# HMI_SENSOR.net
KiCad netlist of a schematic drawn in Altium Designer
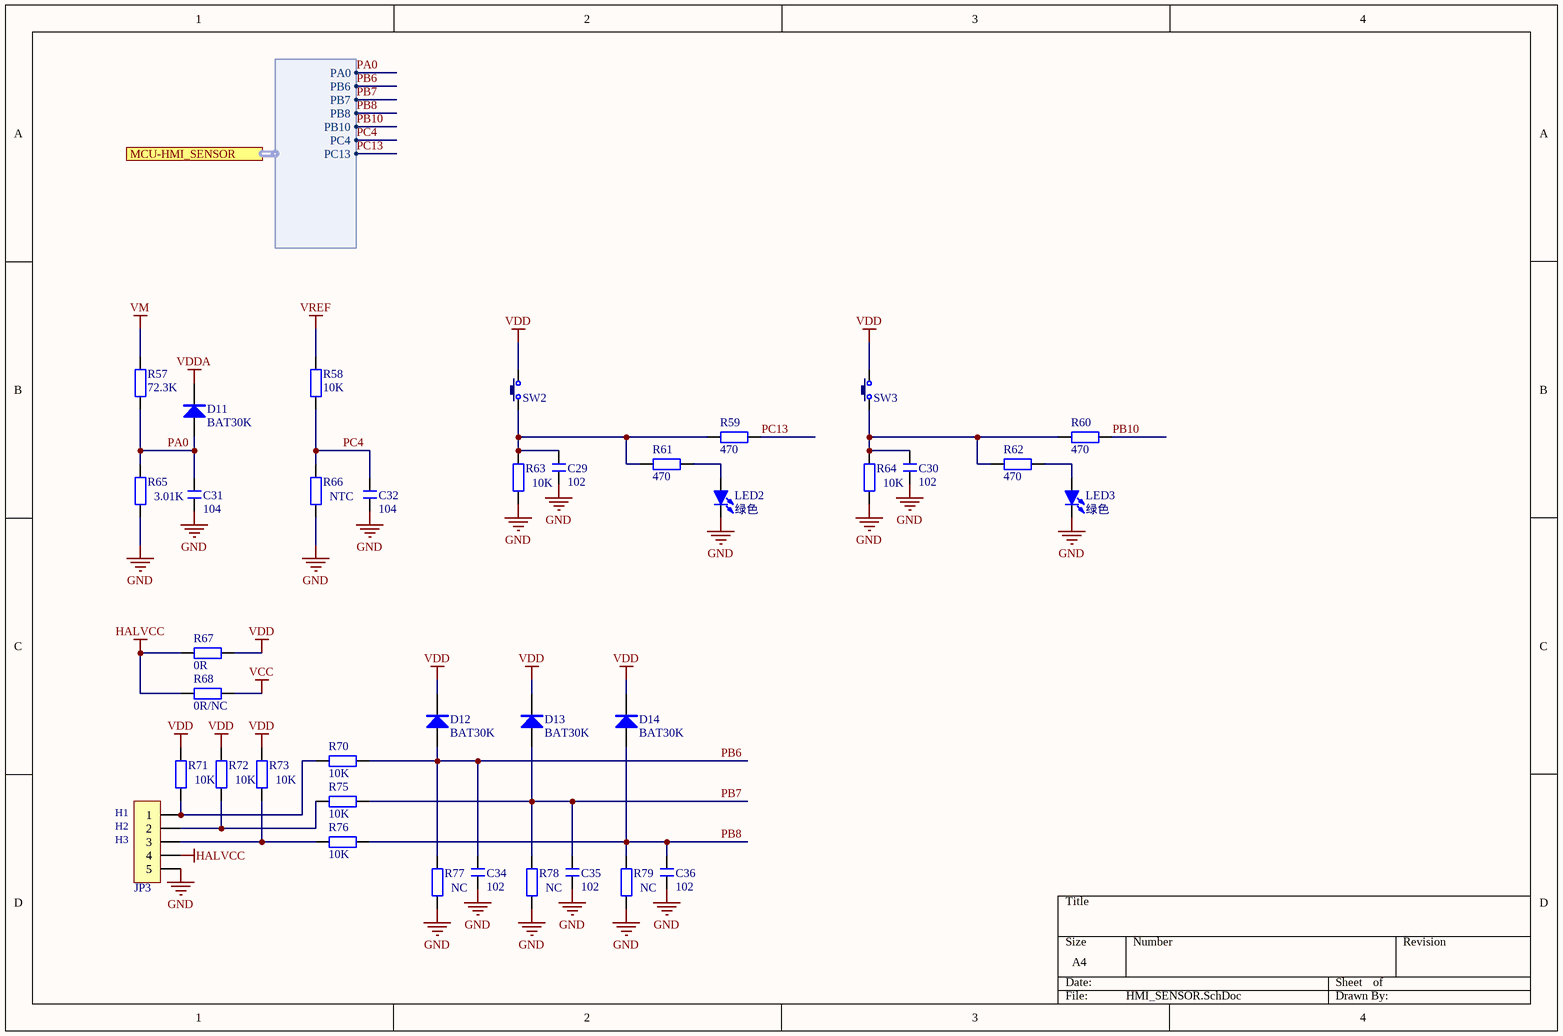
[diagram p0: HMI_SENSOR.SchDoc]

(export (version "E")
  (design (tool "Eeschema 10.0.6"))
  (components
    (comp (ref "C29")
      (value "102")
      (footprint "C 0603_L")
      (description "无极性贴片电容")
      (fields (field (name "版权归属") "源创客"))
      (libsource (lib "3.1   - 电阻-电容-电感") (part "C"))
    )
    (comp (ref "C30")
      (value "102")
      (footprint "C 0603_L")
      (description "无极性贴片电容")
      (fields (field (name "版权归属") "源创客"))
      (libsource (lib "3.1   - 电阻-电容-电感") (part "C"))
    )
    (comp (ref "C31")
      (value "104")
      (footprint "C 0603_L")
      (description "无极性贴片电容")
      (fields (field (name "版权归属") "源创客"))
      (libsource (lib "3.1   - 电阻-电容-电感") (part "C"))
    )
    (comp (ref "C32")
      (value "104")
      (footprint "C 0603_L")
      (description "无极性贴片电容")
      (fields (field (name "版权归属") "源创客"))
      (libsource (lib "3.1   - 电阻-电容-电感") (part "C"))
    )
    (comp (ref "C34")
      (value "102")
      (footprint "C 0603_L")
      (description "无极性贴片电容")
      (fields (field (name "版权归属") "源创客"))
      (libsource (lib "3.1   - 电阻-电容-电感") (part "C"))
    )
    (comp (ref "C35")
      (value "102")
      (footprint "C 0603_L")
      (description "无极性贴片电容")
      (fields (field (name "版权归属") "源创客"))
      (libsource (lib "3.1   - 电阻-电容-电感") (part "C"))
    )
    (comp (ref "C36")
      (value "102")
      (footprint "C 0603_L")
      (description "无极性贴片电容")
      (fields (field (name "版权归属") "源创客"))
      (libsource (lib "3.1   - 电阻-电容-电感") (part "C"))
    )
    (comp (ref "D11")
      (value "BAT30K")
      (footprint "SOD-523")
      (description "肖特基二极管")
      (fields (field (name "版权归属") "源创客"))
      (libsource (lib "8.1   - 二极管-整流桥") (part "SS14"))
    )
    (comp (ref "D12")
      (value "BAT30K")
      (footprint "SOD-523")
      (description "肖特基二极管")
      (fields (field (name "版权归属") "源创客"))
      (libsource (lib "8.1   - 二极管-整流桥") (part "SS14"))
    )
    (comp (ref "D13")
      (value "BAT30K")
      (footprint "SOD-523")
      (description "肖特基二极管")
      (fields (field (name "版权归属") "源创客"))
      (libsource (lib "8.1   - 二极管-整流桥") (part "SS14"))
    )
    (comp (ref "D14")
      (value "BAT30K")
      (footprint "SOD-523")
      (description "肖特基二极管")
      (fields (field (name "版权归属") "源创客"))
      (libsource (lib "8.1   - 二极管-整流桥") (part "SS14"))
    )
    (comp (ref "JP3")
      (value "HDR-1X5")
      (footprint "XH2.54-WI-5P")
      (description "5P接插件")
      (fields (field (name "版权归属") "源创客"))
      (libsource (lib "4.5   - 接插件-脚距2.54") (part "Header 5"))
    )
    (comp (ref "LED2")
      (value "绿色")
      (footprint "LED 0603G")
      (description "贴片LED")
      (fields (field (name "版权归属") "源创客"))
      (libsource (lib "9.1   - LED") (part "LED-SMD"))
    )
    (comp (ref "LED3")
      (value "绿色")
      (footprint "LED 0603G")
      (description "贴片LED")
      (fields (field (name "版权归属") "源创客"))
      (libsource (lib "9.1   - LED") (part "LED-SMD"))
    )
    (comp (ref "R57")
      (value "72.3K")
      (footprint "R 0603_L")
      (description "贴片电阻")
      (fields (field (name "版权归属") "源创客"))
      (libsource (lib "3.1   - 电阻-电容-电感") (part "R"))
    )
    (comp (ref "R58")
      (value "10K")
      (footprint "R 0603_L")
      (description "贴片电阻")
      (fields (field (name "版权归属") "源创客"))
      (libsource (lib "3.1   - 电阻-电容-电感") (part "R"))
    )
    (comp (ref "R59")
      (value "470")
      (footprint "R 0603_L")
      (description "贴片电阻")
      (fields (field (name "版权归属") "源创客"))
      (libsource (lib "3.1   - 电阻-电容-电感") (part "R"))
    )
    (comp (ref "R60")
      (value "470")
      (footprint "R 0603_L")
      (description "贴片电阻")
      (fields (field (name "版权归属") "源创客"))
      (libsource (lib "3.1   - 电阻-电容-电感") (part "R"))
    )
    (comp (ref "R61")
      (value "470")
      (footprint "R 0603_L")
      (description "贴片电阻")
      (fields (field (name "版权归属") "源创客"))
      (libsource (lib "3.1   - 电阻-电容-电感") (part "R"))
    )
    (comp (ref "R62")
      (value "470")
      (footprint "R 0603_L")
      (description "贴片电阻")
      (fields (field (name "版权归属") "源创客"))
      (libsource (lib "3.1   - 电阻-电容-电感") (part "R"))
    )
    (comp (ref "R63")
      (value "10K")
      (footprint "R 0603_L")
      (description "贴片电阻")
      (fields (field (name "版权归属") "源创客"))
      (libsource (lib "3.1   - 电阻-电容-电感") (part "R"))
    )
    (comp (ref "R64")
      (value "10K")
      (footprint "R 0603_L")
      (description "贴片电阻")
      (fields (field (name "版权归属") "源创客"))
      (libsource (lib "3.1   - 电阻-电容-电感") (part "R"))
    )
    (comp (ref "R65")
      (value "3.01K")
      (footprint "R 0603_L")
      (description "贴片电阻")
      (fields (field (name "版权归属") "源创客"))
      (libsource (lib "3.1   - 电阻-电容-电感") (part "R"))
    )
    (comp (ref "R66")
      (value "NTC")
      (footprint "R 0603_M")
      (description "贴片电阻")
      (fields (field (name "版权归属") "源创客"))
      (libsource (lib "3.1   - 电阻-电容-电感") (part "R"))
    )
    (comp (ref "R67")
      (value "0R")
      (footprint "R 0603_L")
      (description "贴片电阻")
      (fields (field (name "版权归属") "源创客"))
      (libsource (lib "3.1   - 电阻-电容-电感") (part "R"))
    )
    (comp (ref "R68")
      (value "0R/NC")
      (footprint "R 0603_L")
      (description "贴片电阻")
      (fields (field (name "版权归属") "源创客"))
      (libsource (lib "3.1   - 电阻-电容-电感") (part "R"))
    )
    (comp (ref "R70")
      (value "10K")
      (footprint "R 0603_L")
      (description "贴片电阻")
      (fields (field (name "版权归属") "源创客"))
      (libsource (lib "3.1   - 电阻-电容-电感") (part "R"))
    )
    (comp (ref "R71")
      (value "10K")
      (footprint "R 0603_L")
      (description "贴片电阻")
      (fields (field (name "版权归属") "源创客"))
      (libsource (lib "3.1   - 电阻-电容-电感") (part "R"))
    )
    (comp (ref "R72")
      (value "10K")
      (footprint "R 0603_L")
      (description "贴片电阻")
      (fields (field (name "版权归属") "源创客"))
      (libsource (lib "3.1   - 电阻-电容-电感") (part "R"))
    )
    (comp (ref "R73")
      (value "10K")
      (footprint "R 0603_L")
      (description "贴片电阻")
      (fields (field (name "版权归属") "源创客"))
      (libsource (lib "3.1   - 电阻-电容-电感") (part "R"))
    )
    (comp (ref "R75")
      (value "10K")
      (footprint "R 0603_L")
      (description "贴片电阻")
      (fields (field (name "版权归属") "源创客"))
      (libsource (lib "3.1   - 电阻-电容-电感") (part "R"))
    )
    (comp (ref "R76")
      (value "10K")
      (footprint "R 0603_L")
      (description "贴片电阻")
      (fields (field (name "版权归属") "源创客"))
      (libsource (lib "3.1   - 电阻-电容-电感") (part "R"))
    )
    (comp (ref "R77")
      (value "NC")
      (footprint "R 0603_L")
      (description "贴片电阻")
      (fields (field (name "版权归属") "源创客"))
      (libsource (lib "3.1   - 电阻-电容-电感") (part "R"))
    )
    (comp (ref "R78")
      (value "NC")
      (footprint "R 0603_L")
      (description "贴片电阻")
      (fields (field (name "版权归属") "源创客"))
      (libsource (lib "3.1   - 电阻-电容-电感") (part "R"))
    )
    (comp (ref "R79")
      (value "NC")
      (footprint "R 0603_L")
      (description "贴片电阻")
      (fields (field (name "版权归属") "源创客"))
      (libsource (lib "3.1   - 电阻-电容-电感") (part "R"))
    )
    (comp (ref "SW2")
      (value "3x6x5")
      (footprint "TSW SMD-3*6*2.5")
      (description "3x6轻触开关")
      (fields (field (name "版权归属") "源创客"))
      (libsource (lib "5.1   - 按键-开关") (part "TSW 3x6"))
    )
    (comp (ref "SW3")
      (value "3x6x5")
      (footprint "TSW SMD-3*6*2.5")
      (description "3x6轻触开关")
      (fields (field (name "版权归属") "源创客"))
      (libsource (lib "5.1   - 按键-开关") (part "TSW 3x6"))
    )
  )
  (nets
    (net (code "2") (name "/PA0") (class "Default")
      (node (ref "C31") (pin "1") (pinfunction "1_1") (pintype "passive"))
      (node (ref "D11") (pin "1") (pinfunction "A_1") (pintype "passive"))
      (node (ref "R57") (pin "2") (pinfunction "2_2") (pintype "passive"))
      (node (ref "R65") (pin "1") (pinfunction "1_1") (pintype "passive"))
    )
    (net (code "3") (name "/PB6") (class "Default")
      (node (ref "C34") (pin "1") (pinfunction "1_1") (pintype "passive"))
      (node (ref "D12") (pin "1") (pinfunction "A_1") (pintype "passive"))
      (node (ref "R70") (pin "2") (pinfunction "2_2") (pintype "passive"))
      (node (ref "R77") (pin "1") (pinfunction "1_1") (pintype "passive"))
    )
    (net (code "4") (name "/PB7") (class "Default")
      (node (ref "C35") (pin "1") (pinfunction "1_1") (pintype "passive"))
      (node (ref "D13") (pin "1") (pinfunction "A_1") (pintype "passive"))
      (node (ref "R75") (pin "2") (pinfunction "2_2") (pintype "passive"))
      (node (ref "R78") (pin "1") (pinfunction "1_1") (pintype "passive"))
    )
    (net (code "5") (name "/PB8") (class "Default")
      (node (ref "C36") (pin "1") (pinfunction "1_1") (pintype "passive"))
      (node (ref "D14") (pin "1") (pinfunction "A_1") (pintype "passive"))
      (node (ref "R76") (pin "2") (pinfunction "2_2") (pintype "passive"))
      (node (ref "R79") (pin "1") (pinfunction "1_1") (pintype "passive"))
    )
    (net (code "6") (name "/PB10") (class "Default")
      (node (ref "R60") (pin "2") (pinfunction "2_2") (pintype "passive"))
    )
    (net (code "7") (name "/PC4") (class "Default")
      (node (ref "C32") (pin "1") (pinfunction "1_1") (pintype "passive"))
      (node (ref "R58") (pin "2") (pinfunction "2_2") (pintype "passive"))
      (node (ref "R66") (pin "1") (pinfunction "1_1") (pintype "passive"))
    )
    (net (code "8") (name "/PC13") (class "Default")
      (node (ref "R59") (pin "2") (pinfunction "2_2") (pintype "passive"))
    )
    (net (code "10") (name "GND") (class "Default")
      (node (ref "C29") (pin "2") (pinfunction "2_2") (pintype "passive"))
      (node (ref "C30") (pin "2") (pinfunction "2_2") (pintype "passive"))
      (node (ref "C31") (pin "2") (pinfunction "2_2") (pintype "passive"))
      (node (ref "C32") (pin "2") (pinfunction "2_2") (pintype "passive"))
      (node (ref "C34") (pin "2") (pinfunction "2_2") (pintype "passive"))
      (node (ref "C35") (pin "2") (pinfunction "2_2") (pintype "passive"))
      (node (ref "C36") (pin "2") (pinfunction "2_2") (pintype "passive"))
      (node (ref "JP3") (pin "5") (pinfunction "5_5") (pintype "passive"))
      (node (ref "LED2") (pin "2") (pinfunction "K_2") (pintype "passive"))
      (node (ref "LED3") (pin "2") (pinfunction "K_2") (pintype "passive"))
      (node (ref "R63") (pin "2") (pinfunction "2_2") (pintype "passive"))
      (node (ref "R64") (pin "2") (pinfunction "2_2") (pintype "passive"))
      (node (ref "R65") (pin "2") (pinfunction "2_2") (pintype "passive"))
      (node (ref "R66") (pin "2") (pinfunction "2_2") (pintype "passive"))
      (node (ref "R77") (pin "2") (pinfunction "2_2") (pintype "passive"))
      (node (ref "R78") (pin "2") (pinfunction "2_2") (pintype "passive"))
      (node (ref "R79") (pin "2") (pinfunction "2_2") (pintype "passive"))
    )
    (net (code "11") (name "HALVCC") (class "Default")
      (node (ref "JP3") (pin "4") (pinfunction "4_4") (pintype "passive"))
      (node (ref "R67") (pin "2") (pinfunction "2_2") (pintype "passive"))
      (node (ref "R68") (pin "2") (pinfunction "2_2") (pintype "passive"))
    )
    (net (code "12") (name "Net-(C29-Pad1)") (class "Default")
      (node (ref "C29") (pin "1") (pinfunction "1_1") (pintype "passive"))
      (node (ref "R59") (pin "1") (pinfunction "1_1") (pintype "passive"))
      (node (ref "R61") (pin "1") (pinfunction "1_1") (pintype "passive"))
      (node (ref "R63") (pin "1") (pinfunction "1_1") (pintype "passive"))
      (node (ref "SW2") (pin "1") (pinfunction "1_1") (pintype "passive"))
    )
    (net (code "13") (name "Net-(C30-Pad1)") (class "Default")
      (node (ref "C30") (pin "1") (pinfunction "1_1") (pintype "passive"))
      (node (ref "R60") (pin "1") (pinfunction "1_1") (pintype "passive"))
      (node (ref "R62") (pin "1") (pinfunction "1_1") (pintype "passive"))
      (node (ref "R64") (pin "1") (pinfunction "1_1") (pintype "passive"))
      (node (ref "SW3") (pin "1") (pinfunction "1_1") (pintype "passive"))
    )
    (net (code "14") (name "Net-(JP3-Pad1)") (class "Default")
      (node (ref "JP3") (pin "1") (pinfunction "1_1") (pintype "passive"))
      (node (ref "R70") (pin "1") (pinfunction "1_1") (pintype "passive"))
      (node (ref "R71") (pin "2") (pinfunction "2_2") (pintype "passive"))
    )
    (net (code "15") (name "Net-(JP3-Pad2)") (class "Default")
      (node (ref "JP3") (pin "2") (pinfunction "2_2") (pintype "passive"))
      (node (ref "R72") (pin "2") (pinfunction "2_2") (pintype "passive"))
      (node (ref "R75") (pin "1") (pinfunction "1_1") (pintype "passive"))
    )
    (net (code "16") (name "Net-(JP3-Pad3)") (class "Default")
      (node (ref "JP3") (pin "3") (pinfunction "3_3") (pintype "passive"))
      (node (ref "R73") (pin "2") (pinfunction "2_2") (pintype "passive"))
      (node (ref "R76") (pin "1") (pinfunction "1_1") (pintype "passive"))
    )
    (net (code "17") (name "Net-(LED2-A)") (class "Default")
      (node (ref "LED2") (pin "1") (pinfunction "A_1") (pintype "passive"))
      (node (ref "R61") (pin "2") (pinfunction "2_2") (pintype "passive"))
    )
    (net (code "18") (name "Net-(LED3-A)") (class "Default")
      (node (ref "LED3") (pin "1") (pinfunction "A_1") (pintype "passive"))
      (node (ref "R62") (pin "2") (pinfunction "2_2") (pintype "passive"))
    )
    (net (code "19") (name "VCC") (class "Default")
      (node (ref "R68") (pin "1") (pinfunction "1_1") (pintype "passive"))
    )
    (net (code "20") (name "VDD") (class "Default")
      (node (ref "D12") (pin "2") (pinfunction "K_2") (pintype "passive"))
      (node (ref "D13") (pin "2") (pinfunction "K_2") (pintype "passive"))
      (node (ref "D14") (pin "2") (pinfunction "K_2") (pintype "passive"))
      (node (ref "R67") (pin "1") (pinfunction "1_1") (pintype "passive"))
      (node (ref "R71") (pin "1") (pinfunction "1_1") (pintype "passive"))
      (node (ref "R72") (pin "1") (pinfunction "1_1") (pintype "passive"))
      (node (ref "R73") (pin "1") (pinfunction "1_1") (pintype "passive"))
      (node (ref "SW2") (pin "2") (pinfunction "2_2") (pintype "passive"))
      (node (ref "SW3") (pin "2") (pinfunction "2_2") (pintype "passive"))
    )
    (net (code "21") (name "VDDA") (class "Default")
      (node (ref "D11") (pin "2") (pinfunction "K_2") (pintype "passive"))
    )
    (net (code "22") (name "VM") (class "Default")
      (node (ref "R57") (pin "1") (pinfunction "1_1") (pintype "passive"))
    )
    (net (code "23") (name "VREF") (class "Default")
      (node (ref "R58") (pin "1") (pinfunction "1_1") (pintype "passive"))
    )
  )
)
